# 16V2_EDA.net
KiCad netlist of a schematic drawn in EasyEDA Pro
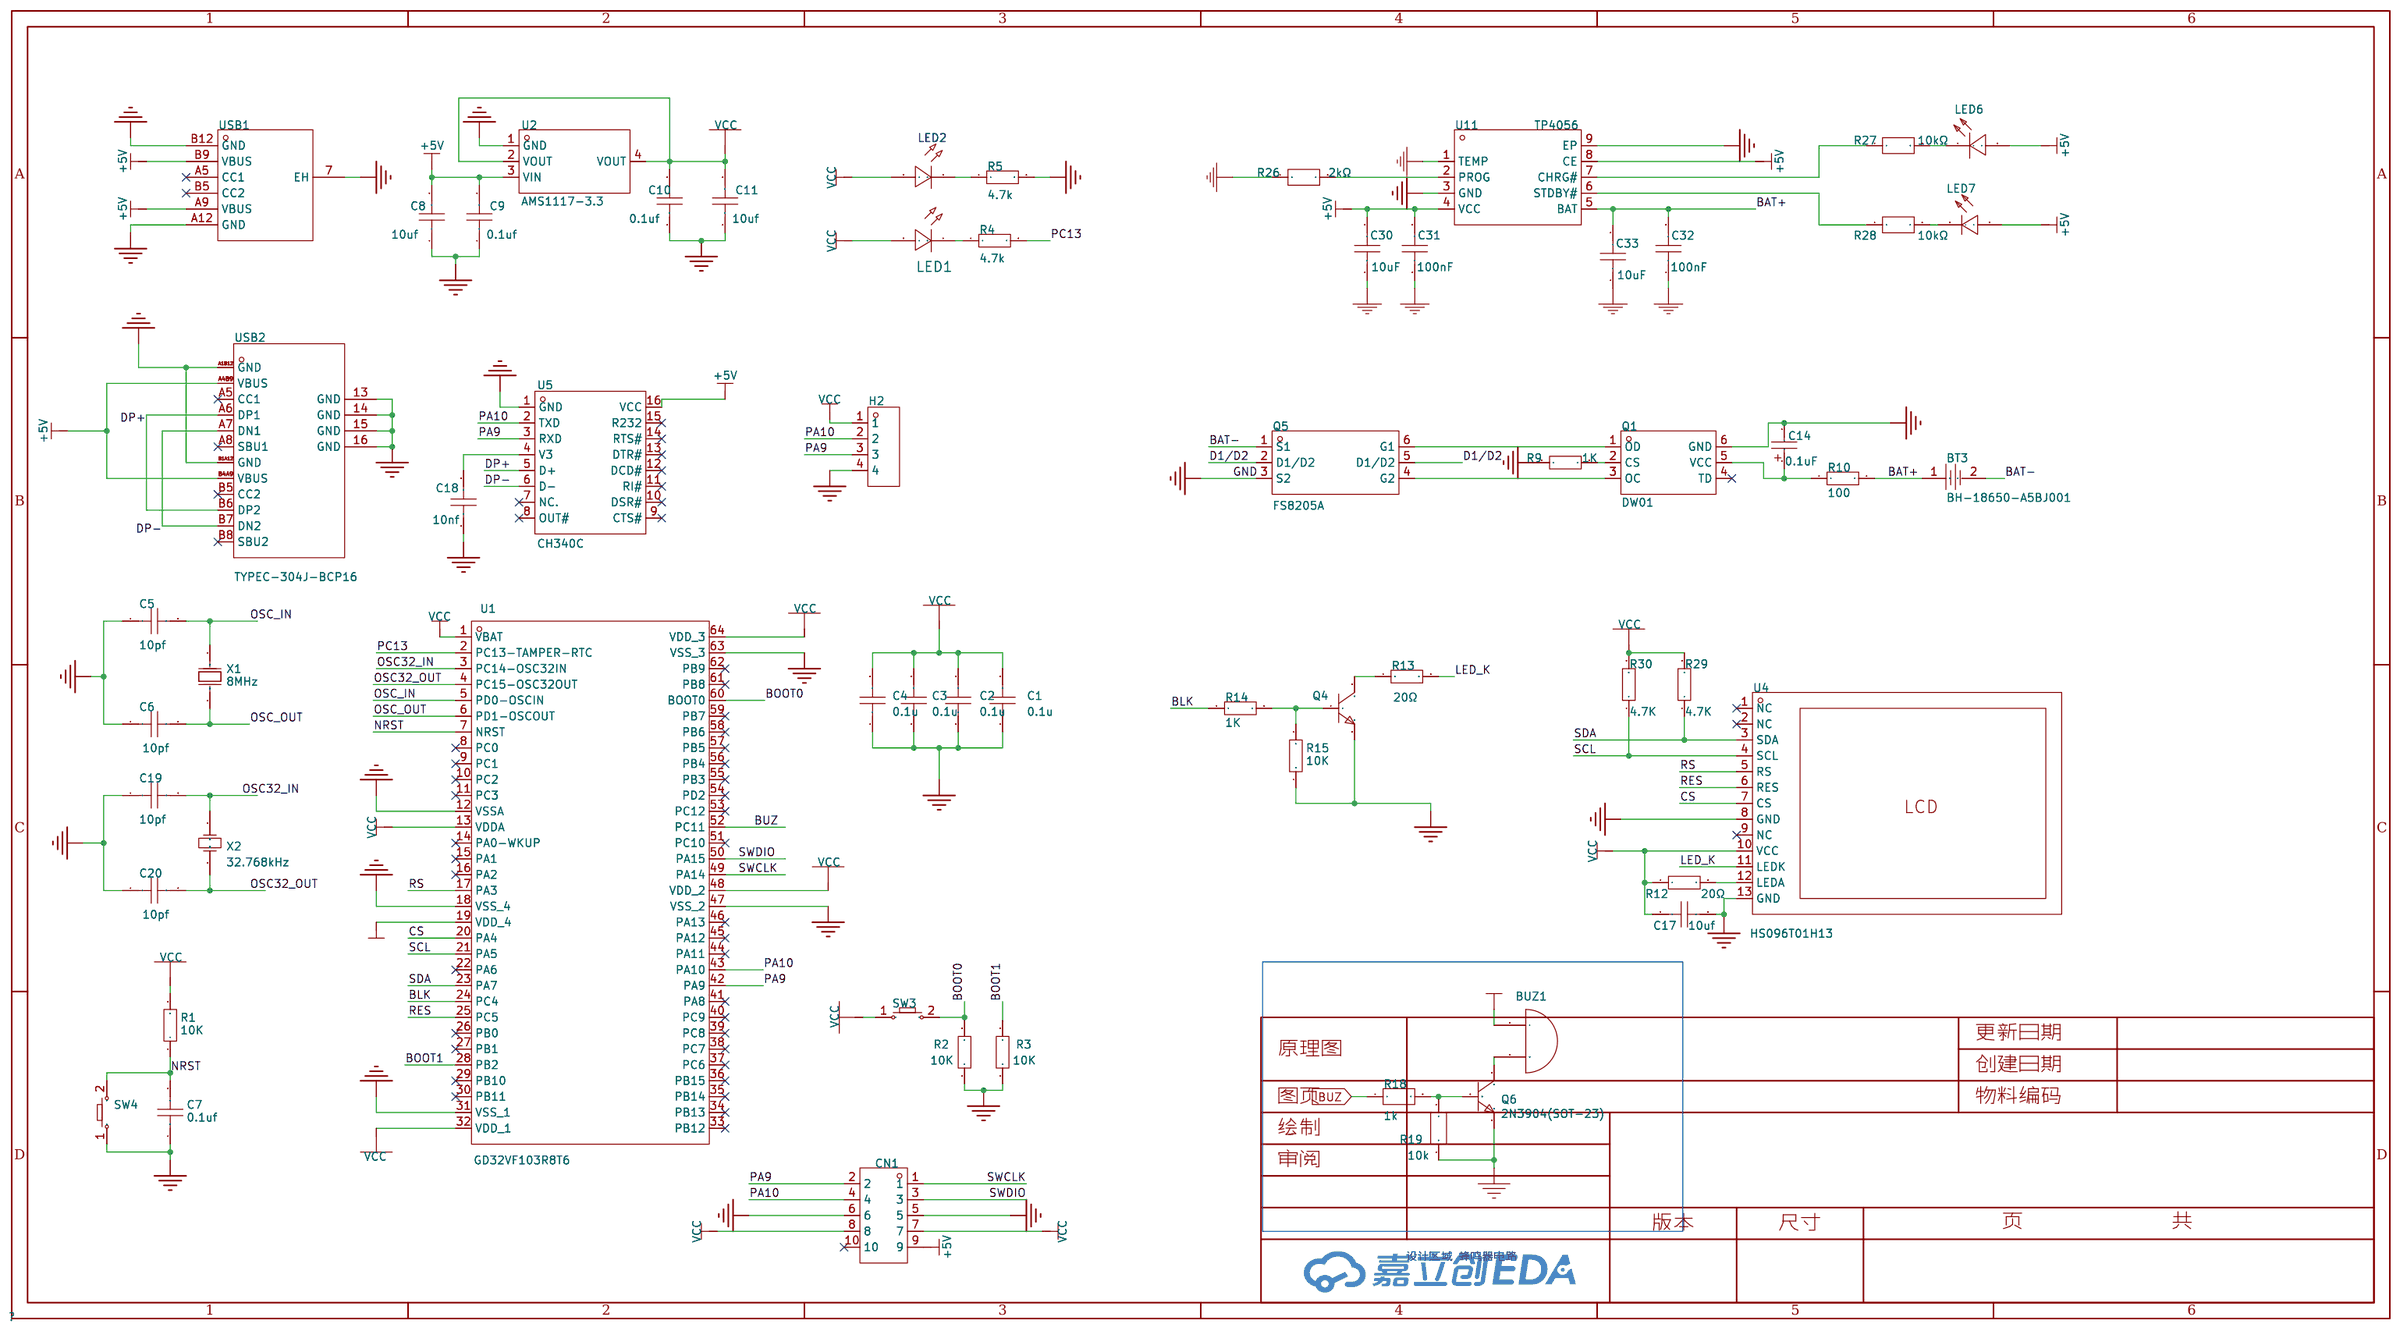
[diagram p0: schematic sheet]

(export (version "E")
  (design (tool "Eeschema 10.0.6"))
  (components
    (comp (ref "BT3")
      (value "BH-18650-A5BJ001")
      (footprint "easyedapro:BAT-TH_18650-A5BJ001")
      (description "BHNi DIP 适用电池18650电芯//电池底座/卧式DIP 电池盒/电池座 材质：PP  镀镍 ，")
      (fields (field (name "Manufacturer") "MYOUNG(美阳)"))
      (libsource (lib "easyedapro") (part "BH-18650-A5BJ001"))
    )
    (comp (ref "BUZ1") (value "BUZ1") (libsource (lib "easyedapro") (part "BUZ1")))
    (comp (ref "C1")
      (value "0.1u")
      (footprint "easyedapro:C0603")
      (libsource (lib "easyedapro") (part "capacitance"))
    )
    (comp (ref "C2")
      (value "0.1u")
      (footprint "easyedapro:C0603")
      (libsource (lib "easyedapro") (part "capacitance"))
    )
    (comp (ref "C3")
      (value "0.1u")
      (footprint "easyedapro:C0603")
      (libsource (lib "easyedapro") (part "capacitance"))
    )
    (comp (ref "C4")
      (value "0.1u")
      (footprint "easyedapro:C0603")
      (libsource (lib "easyedapro") (part "capacitance"))
    )
    (comp (ref "C5")
      (value "10pf")
      (footprint "easyedapro:C0603")
      (libsource (lib "easyedapro") (part "capacitance"))
    )
    (comp (ref "C6")
      (value "10pf")
      (footprint "easyedapro:C0603")
      (libsource (lib "easyedapro") (part "capacitance"))
    )
    (comp (ref "C7")
      (value "0.1uf")
      (footprint "easyedapro:C0603")
      (libsource (lib "easyedapro") (part "capacitance"))
    )
    (comp (ref "C8")
      (value "10uf")
      (footprint "easyedapro:C0603")
      (libsource (lib "easyedapro") (part "capacitance"))
    )
    (comp (ref "C9")
      (value "0.1uf")
      (footprint "easyedapro:C0603")
      (libsource (lib "easyedapro") (part "capacitance"))
    )
    (comp (ref "C10")
      (value "0.1uf")
      (footprint "easyedapro:C0603")
      (libsource (lib "easyedapro") (part "capacitance"))
    )
    (comp (ref "C11")
      (value "10uf")
      (footprint "easyedapro:C0603")
      (libsource (lib "easyedapro") (part "capacitance"))
    )
    (comp (ref "C14")
      (value "0.1uF")
      (footprint "easyedapro:C_Ele_SMD_3x5.4mm")
      (libsource (lib "easyedapro") (part "CAP"))
    )
    (comp (ref "C17")
      (value "10uf")
      (footprint "easyedapro:C0603")
      (libsource (lib "easyedapro") (part "capacitance"))
    )
    (comp (ref "C18")
      (value "10nf")
      (footprint "easyedapro:C0603")
      (libsource (lib "easyedapro") (part "capacitance"))
    )
    (comp (ref "C19")
      (value "10pf")
      (footprint "easyedapro:C0603")
      (libsource (lib "easyedapro") (part "capacitance"))
    )
    (comp (ref "C20")
      (value "10pf")
      (footprint "easyedapro:C0603")
      (libsource (lib "easyedapro") (part "capacitance"))
    )
    (comp (ref "C30")
      (value "10uF")
      (fields (field (name "Manufacturer") "SAMSUNG(三星)"))
      (libsource (lib "easyedapro") (part "10u"))
    )
    (comp (ref "C31")
      (value "100nF")
      (fields (field (name "Manufacturer") "YAGEO(国巨)"))
      (libsource (lib "easyedapro") (part "0.1u"))
    )
    (comp (ref "C32")
      (value "100nF")
      (fields (field (name "Manufacturer") "YAGEO(国巨)"))
      (libsource (lib "easyedapro") (part "0.1u"))
    )
    (comp (ref "C33")
      (value "10uF")
      (fields (field (name "Manufacturer") "SAMSUNG(三星)"))
      (libsource (lib "easyedapro") (part "10u"))
    )
    (comp (ref "CN1") (value "ZX-PZ2.54-2-5PZZ") (libsource (lib "easyedapro") (part "phd-2*5a_c2847737")))
    (comp (ref "H2")
      (value "2.54-1*4P反弯排针")
      (footprint "easyedapro:HDR-TH_4P-P2.54-H-M-W10.4")
      (fields (field (name "Manufacturer") "BOOMELE(博穆精密)"))
      (libsource (lib "easyedapro") (part "2.54-1*4P反弯排针"))
    )
    (comp (ref "LED1")
      (value "~")
      (footprint "easyedapro:LED_0603")
      (libsource (lib "easyedapro") (part "LED_R"))
    )
    (comp (ref "LED2")
      (value "~")
      (footprint "easyedapro:LED_0603")
      (libsource (lib "easyedapro") (part "LED_G"))
    )
    (comp (ref "LED6")
      (value "KT-0603R")
      (fields (field (name "Manufacturer") "KENTO"))
      (libsource (lib "easyedapro") (part "KT-0603R"))
    )
    (comp (ref "LED7") (value "NCD0603B1") (libsource (lib "easyedapro") (part "fc-da1608bk-470h10")))
    (comp (ref "Q1")
      (value "DW01")
      (footprint "easyedapro:SOT-23-6_L2.9-W1.6-P0.95-LS2.8-BR")
      (fields (field (name "Manufacturer") "Hottech(合科泰)"))
      (libsource (lib "easyedapro") (part "DW01"))
    )
    (comp (ref "Q4")
      (value "~")
      (footprint "easyedapro:S8050_SOT-23")
      (libsource (lib "easyedapro") (part "NPN"))
    )
    (comp (ref "Q5")
      (value "FS8205A")
      (footprint "easyedapro:SOT-23-6_L2.9-W1.6-P0.95-LS2.8-BR")
      (fields (field (name "Manufacturer") "TECH PUBLIC(台舟)"))
      (libsource (lib "easyedapro") (part "FS8205A_C2830320"))
    )
    (comp (ref "Q6")
      (value "2N3904(SOT-23)")
      (fields (field (name "Manufacturer Part") "2n3904S-RTK/PS") (field (name "Manufacturer") "KEC"))
      (libsource (lib "easyedapro") (part "2N3904(SOT-23)"))
    )
    (comp (ref "R1") (value "10K") (libsource (lib "easyedapro") (part "电阻")))
    (comp (ref "R2") (value "10K") (libsource (lib "easyedapro") (part "电阻")))
    (comp (ref "R3") (value "10K") (libsource (lib "easyedapro") (part "电阻")))
    (comp (ref "R4") (value "4.7k") (libsource (lib "easyedapro") (part "电阻")))
    (comp (ref "R5") (value "4.7k") (libsource (lib "easyedapro") (part "电阻")))
    (comp (ref "R9") (value "1K") (libsource (lib "easyedapro") (part "电阻")))
    (comp (ref "R10") (value "100") (libsource (lib "easyedapro") (part "电阻")))
    (comp (ref "R12") (value "20Ω") (libsource (lib "easyedapro") (part "电阻")))
    (comp (ref "R13") (value "20Ω") (libsource (lib "easyedapro") (part "电阻")))
    (comp (ref "R14") (value "1K") (libsource (lib "easyedapro") (part "电阻")))
    (comp (ref "R15") (value "10K") (libsource (lib "easyedapro") (part "电阻")))
    (comp (ref "R18") (value "1k") (libsource (lib "easyedapro") (part "1k")))
    (comp (ref "R19") (value "10k") (libsource (lib "easyedapro") (part "10k")))
    (comp (ref "R26")
      (value "2kΩ")
      (fields (field (name "Manufacturer") "UNI-ROYAL(厚声)"))
      (libsource (lib "easyedapro") (part "2k"))
    )
    (comp (ref "R27")
      (value "10kΩ")
      (fields (field (name "Manufacturer") "UNI-ROYAL(厚声)"))
      (libsource (lib "easyedapro") (part "10k"))
    )
    (comp (ref "R28")
      (value "10kΩ")
      (fields (field (name "Manufacturer") "UNI-ROYAL(厚声)"))
      (libsource (lib "easyedapro") (part "10k"))
    )
    (comp (ref "R29")
      (value "4.7K")
      (footprint "easyedapro:R0603")
      (libsource (lib "easyedapro") (part "电阻"))
    )
    (comp (ref "R30")
      (value "4.7K")
      (footprint "easyedapro:R0603")
      (libsource (lib "easyedapro") (part "电阻"))
    )
    (comp (ref "SW3")
      (value "~")
      (footprint "easyedapro:Key_SMD_3x4x2")
      (libsource (lib "easyedapro") (part "轻触按键x2"))
    )
    (comp (ref "SW4")
      (value "~")
      (footprint "easyedapro:Key_SMD_3x4x2")
      (libsource (lib "easyedapro") (part "轻触按键x2"))
    )
    (comp (ref "U1")
      (value "GD32VF103R8T6")
      (footprint "easyedapro:LQFP-64_L10.0-W10.0-P0.50-LS12.0-BL")
      (description "CPU内核:RISC-V;程序存储容量:64KB;RAM总容量:20KB;GPIO端口数量:51;工作电压范围:-;CPU最大主频:108MHz;程序存储器类型:FLASH;")
      (fields (field (name "Manufacturer") "GigaDevice(兆易创新)"))
      (libsource (lib "easyedapro") (part "GD32VF103R8T6"))
    )
    (comp (ref "U2")
      (value "AMS1117-3.3")
      (footprint "easyedapro:SOT-223-3_L6.5-W3.4-P2.30-LS7.0-BR")
      (description "输出类型:固定;最大输入电压:-;输出电压:3.3V;最大输出电流:1A;电源纹波抑制比(PSRR):72dB@(120Hz);输出极性:正极;")
      (fields (field (name "Manufacturer") "AMS"))
      (libsource (lib "easyedapro") (part "AMS1117-3.3"))
    )
    (comp (ref "U4")
      (value "HS096T01H13")
      (footprint "easyedapro:LCD-SMD_HS096T01H13")
      (description "主控芯片:ST7735;尺寸(inch):0.96;")
      (fields (field (name "Manufacturer") "HS(汉昇)"))
      (libsource (lib "easyedapro") (part "HS096T01H13"))
    )
    (comp (ref "U5")
      (value "CH340C")
      (footprint "easyedapro:SOP-16_L10.0-W3.9-P1.27-LS6.0-BL")
      (description "应用功能:收发器;接口协议:USB 2.0;数据速率:2Mbps;")
      (fields (field (name "Manufacturer") "WCH(南京沁恒)"))
      (libsource (lib "easyedapro") (part "CH340C"))
    )
    (comp (ref "U11")
      (value "TP4056")
      (fields (field (name "Manufacturer") "UMW(友台半导体)"))
      (libsource (lib "easyedapro") (part "TP4056_C725790"))
    )
    (comp (ref "USB1")
      (value "TYPE-C 6P")
      (footprint "easyedapro:TYPE-C-SMD_TYPE-C-6P")
      (description "连接器类型:Type-C;标准:-;公母:母;端口数量:1;触点数量:6P;安装方式:卧贴;额定电流 - 电源:-;工作温度范围:-40°C~+85°C;")
      (fields (field (name "Manufacturer") "SHOU HAN(首韩)"))
      (libsource (lib "easyedapro") (part "TYPE-C 6P"))
    )
    (comp (ref "USB2")
      (value "TYPEC-304J-BCP16")
      (footprint "easyedapro:USB-C-SMD_TYPEC-304J-BCP16")
      (fields (field (name "Manufacturer") "XUNPU(讯普)"))
      (libsource (lib "easyedapro") (part "TYPEC-304J-BCP16"))
    )
    (comp (ref "X1")
      (value "8MHz")
      (footprint "easyedapro:CRYSTAL-SMD_L11.5-W4.8-LS12.7")
      (description "晶振类型:贴片晶振;频率:8MHz;常温频差:±20ppm;外接负载电容:20pF;频率稳定度(全温):±30ppm;")
      (fields (field (name "Manufacturer Part") "X49SM8MSD2SC") (field (name "Manufacturer") "YXC(扬兴晶振)"))
      (libsource (lib "easyedapro") (part "X49SM8MSD2SC"))
    )
    (comp (ref "X2")
      (value "32.768kHz")
      (footprint "easyedapro:OSC-TH_BD3.1-P0.8-D0.3")
      (description "晶振类型:直插晶振;频率:32.768kHz;常温频差:±10ppm;外接负载电容:12.5pF;频率稳定度(全温):-;")
      (fields (field (name "Manufacturer Part") "X308032768KGB2SC") (field (name "Manufacturer") "YXC(扬兴晶振)"))
      (libsource (lib "easyedapro") (part "X308032768KGB2SC"))
    )
  )
  (nets
    (net (code "1") (name "+5V") (class "Default")
      (node (ref "C30") (pin "2") (pinfunction "2_2") (pintype "unspecified"))
      (node (ref "C31") (pin "2") (pinfunction "2_2") (pintype "unspecified"))
      (node (ref "C8") (pin "2") (pinfunction "2_2") (pintype "input"))
      (node (ref "C9") (pin "2") (pinfunction "2_2") (pintype "input"))
      (node (ref "CN1") (pin "9") (pinfunction "9_9") (pintype "unspecified"))
      (node (ref "LED6") (pin "2") (pinfunction "A_2") (pintype "unspecified"))
      (node (ref "LED7") (pin "2") (pinfunction "+_2") (pintype "input"))
      (node (ref "U11") (pin "4") (pinfunction "VCC_4") (pintype "unspecified"))
      (node (ref "U11") (pin "8") (pinfunction "CE_8") (pintype "unspecified"))
      (node (ref "U2") (pin "3") (pinfunction "VIN_3") (pintype "unspecified"))
      (node (ref "U5") (pin "16") (pinfunction "VCC_16") (pintype "unspecified"))
      (node (ref "USB1") (pin "A9") (pinfunction "VBUS_A9") (pintype "unspecified"))
      (node (ref "USB1") (pin "B9") (pinfunction "VBUS_B9") (pintype "unspecified"))
      (node (ref "USB2") (pin "A4B9") (pinfunction "VBUS_A4B9") (pintype "unspecified"))
      (node (ref "USB2") (pin "B4A9") (pinfunction "VBUS_B4A9") (pintype "unspecified"))
    )
    (net (code "2") (name "/BAT+") (class "Default")
      (node (ref "BT3") (pin "1") (pinfunction "1_1") (pintype "input"))
      (node (ref "C32") (pin "2") (pinfunction "2_2") (pintype "unspecified"))
      (node (ref "C33") (pin "2") (pinfunction "2_2") (pintype "unspecified"))
      (node (ref "R10") (pin "2") (pinfunction "2_2") (pintype "input"))
      (node (ref "U11") (pin "5") (pinfunction "BAT_5") (pintype "unspecified"))
    )
    (net (code "3") (name "/BAT-") (class "Default")
      (node (ref "BT3") (pin "2") (pinfunction "2_2") (pintype "input"))
      (node (ref "Q5") (pin "1") (pinfunction "S1_1") (pintype "unspecified"))
    )
    (net (code "4") (name "/BLK") (class "Default")
      (node (ref "R14") (pin "1") (pinfunction "1_1") (pintype "input"))
      (node (ref "U1") (pin "24") (pinfunction "PC4_24") (pintype "input"))
    )
    (net (code "5") (name "/BOOT0") (class "Default")
      (node (ref "R2") (pin "2") (pinfunction "2_2") (pintype "input"))
      (node (ref "SW3") (pin "2") (pinfunction "2_2") (pintype "input"))
      (node (ref "U1") (pin "60") (pinfunction "BOOT0_60") (pintype "input"))
    )
    (net (code "6") (name "/BOOT1") (class "Default")
      (node (ref "R3") (pin "2") (pinfunction "2_2") (pintype "input"))
      (node (ref "U1") (pin "28") (pinfunction "PB2_28") (pintype "input"))
    )
    (net (code "7") (name "/CS") (class "Default")
      (node (ref "U1") (pin "20") (pinfunction "PA4_20") (pintype "input"))
      (node (ref "U4") (pin "7") (pinfunction "CS_7") (pintype "unspecified"))
    )
    (net (code "8") (name "/D1{slash}D2") (class "Default")
      (node (ref "Q5") (pin "2") (pinfunction "D1/D2_2") (pintype "unspecified"))
      (node (ref "Q5") (pin "5") (pinfunction "D1/D2_5") (pintype "unspecified"))
    )
    (net (code "9") (name "/DP+") (class "Default")
      (node (ref "U5") (pin "5") (pinfunction "D+_5") (pintype "unspecified"))
      (node (ref "USB2") (pin "A6") (pinfunction "DP1_A6") (pintype "unspecified"))
      (node (ref "USB2") (pin "B6") (pinfunction "DP2_B6") (pintype "unspecified"))
    )
    (net (code "10") (name "/DP-") (class "Default")
      (node (ref "U5") (pin "6") (pinfunction "D-_6") (pintype "unspecified"))
      (node (ref "USB2") (pin "A7") (pinfunction "DN1_A7") (pintype "unspecified"))
      (node (ref "USB2") (pin "B7") (pinfunction "DN2_B7") (pintype "unspecified"))
    )
    (net (code "11") (name "/LED_K") (class "Default")
      (node (ref "R13") (pin "2") (pinfunction "2_2") (pintype "input"))
      (node (ref "U4") (pin "11") (pinfunction "LEDK_11") (pintype "unspecified"))
    )
    (net (code "12") (name "/NRST") (class "Default")
      (node (ref "C7") (pin "2") (pinfunction "2_2") (pintype "input"))
      (node (ref "R1") (pin "1") (pinfunction "1_1") (pintype "input"))
      (node (ref "SW4") (pin "2") (pinfunction "2_2") (pintype "input"))
      (node (ref "U1") (pin "7") (pinfunction "NRST_7") (pintype "input"))
    )
    (net (code "13") (name "/OSC32_IN") (class "Default")
      (node (ref "C19") (pin "2") (pinfunction "2_2") (pintype "input"))
      (node (ref "U1") (pin "3") (pinfunction "PC14-OSC32IN_3") (pintype "input"))
      (node (ref "X2") (pin "1") (pinfunction "OSC1_1") (pintype "unspecified"))
    )
    (net (code "14") (name "/OSC32_OUT") (class "Default")
      (node (ref "C20") (pin "2") (pinfunction "2_2") (pintype "input"))
      (node (ref "U1") (pin "4") (pinfunction "PC15-OSC32OUT_4") (pintype "input"))
      (node (ref "X2") (pin "2") (pinfunction "OSC2_2") (pintype "unspecified"))
    )
    (net (code "15") (name "/OSC_IN") (class "Default")
      (node (ref "C5") (pin "2") (pinfunction "2_2") (pintype "input"))
      (node (ref "U1") (pin "5") (pinfunction "PD0-OSCIN_5") (pintype "input"))
      (node (ref "X1") (pin "1") (pinfunction "OSC1_1") (pintype "input"))
    )
    (net (code "16") (name "/OSC_OUT") (class "Default")
      (node (ref "C6") (pin "2") (pinfunction "2_2") (pintype "input"))
      (node (ref "U1") (pin "6") (pinfunction "PD1-OSCOUT_6") (pintype "input"))
      (node (ref "X1") (pin "2") (pinfunction "OSC2_2") (pintype "input"))
    )
    (net (code "17") (name "/PA9") (class "Default")
      (node (ref "CN1") (pin "2") (pinfunction "2_2") (pintype "unspecified"))
      (node (ref "H2") (pin "3") (pinfunction "3_3") (pintype "unspecified"))
      (node (ref "U1") (pin "42") (pinfunction "PA9_42") (pintype "input"))
      (node (ref "U5") (pin "3") (pinfunction "RXD_3") (pintype "unspecified"))
    )
    (net (code "18") (name "/PA10") (class "Default")
      (node (ref "CN1") (pin "4") (pinfunction "4_4") (pintype "unspecified"))
      (node (ref "H2") (pin "2") (pinfunction "2_2") (pintype "unspecified"))
      (node (ref "U1") (pin "43") (pinfunction "PA10_43") (pintype "input"))
      (node (ref "U5") (pin "2") (pinfunction "TXD_2") (pintype "unspecified"))
    )
    (net (code "19") (name "/PC13") (class "Default")
      (node (ref "R4") (pin "2") (pinfunction "2_2") (pintype "input"))
      (node (ref "U1") (pin "2") (pinfunction "PC13-TAMPER-RTC_2") (pintype "input"))
    )
    (net (code "20") (name "/RES") (class "Default")
      (node (ref "U1") (pin "25") (pinfunction "PC5_25") (pintype "input"))
      (node (ref "U4") (pin "6") (pinfunction "RES_6") (pintype "unspecified"))
    )
    (net (code "21") (name "/RS") (class "Default")
      (node (ref "U1") (pin "17") (pinfunction "PA3_17") (pintype "input"))
      (node (ref "U4") (pin "5") (pinfunction "RS_5") (pintype "unspecified"))
    )
    (net (code "22") (name "/SCL") (class "Default")
      (node (ref "R30") (pin "1") (pinfunction "1_1") (pintype "input"))
      (node (ref "U1") (pin "21") (pinfunction "PA5_21") (pintype "input"))
      (node (ref "U4") (pin "4") (pinfunction "SCL_4") (pintype "unspecified"))
    )
    (net (code "23") (name "/SDA") (class "Default")
      (node (ref "R29") (pin "1") (pinfunction "1_1") (pintype "input"))
      (node (ref "U1") (pin "23") (pinfunction "PA7_23") (pintype "input"))
      (node (ref "U4") (pin "3") (pinfunction "SDA_3") (pintype "unspecified"))
    )
    (net (code "24") (name "/SWCLK") (class "Default")
      (node (ref "CN1") (pin "1") (pinfunction "1_1") (pintype "unspecified"))
      (node (ref "U1") (pin "49") (pinfunction "PA14_49") (pintype "input"))
    )
    (net (code "25") (name "/SWDIO") (class "Default")
      (node (ref "CN1") (pin "3") (pinfunction "3_3") (pintype "unspecified"))
      (node (ref "U1") (pin "50") (pinfunction "PA15_50") (pintype "input"))
    )
    (net (code "26") (name "BUZ") (class "Default")
      (node (ref "R18") (pin "1") (pinfunction "1_1") (pintype "input"))
      (node (ref "U1") (pin "52") (pinfunction "PC11_52") (pintype "input"))
    )
    (net (code "27") (name "GND") (class "Default")
      (node (ref "C1") (pin "1") (pinfunction "1_1") (pintype "input"))
      (node (ref "C10") (pin "1") (pinfunction "1_1") (pintype "input"))
      (node (ref "C11") (pin "1") (pinfunction "1_1") (pintype "input"))
      (node (ref "C14") (pin "2") (pinfunction "2_2") (pintype "input"))
      (node (ref "C17") (pin "2") (pinfunction "2_2") (pintype "input"))
      (node (ref "C18") (pin "1") (pinfunction "1_1") (pintype "input"))
      (node (ref "C19") (pin "1") (pinfunction "1_1") (pintype "input"))
      (node (ref "C2") (pin "1") (pinfunction "1_1") (pintype "input"))
      (node (ref "C20") (pin "1") (pinfunction "1_1") (pintype "input"))
      (node (ref "C3") (pin "1") (pinfunction "1_1") (pintype "input"))
      (node (ref "C30") (pin "1") (pinfunction "1_1") (pintype "unspecified"))
      (node (ref "C31") (pin "1") (pinfunction "1_1") (pintype "unspecified"))
      (node (ref "C32") (pin "1") (pinfunction "1_1") (pintype "unspecified"))
      (node (ref "C33") (pin "1") (pinfunction "1_1") (pintype "unspecified"))
      (node (ref "C4") (pin "1") (pinfunction "1_1") (pintype "input"))
      (node (ref "C5") (pin "1") (pinfunction "1_1") (pintype "input"))
      (node (ref "C6") (pin "1") (pinfunction "1_1") (pintype "input"))
      (node (ref "C7") (pin "1") (pinfunction "1_1") (pintype "input"))
      (node (ref "C8") (pin "1") (pinfunction "1_1") (pintype "input"))
      (node (ref "C9") (pin "1") (pinfunction "1_1") (pintype "input"))
      (node (ref "CN1") (pin "5") (pinfunction "5_5") (pintype "unspecified"))
      (node (ref "CN1") (pin "6") (pinfunction "6_6") (pintype "unspecified"))
      (node (ref "H2") (pin "4") (pinfunction "4_4") (pintype "unspecified"))
      (node (ref "Q1") (pin "6") (pinfunction "GND_6") (pintype "input"))
      (node (ref "Q4") (pin "2") (pinfunction "2_2") (pintype "unspecified"))
      (node (ref "Q5") (pin "3") (pinfunction "S2_3") (pintype "unspecified"))
      (node (ref "Q6") (pin "1") (pinfunction "E_1") (pintype "input"))
      (node (ref "R15") (pin "1") (pinfunction "1_1") (pintype "input"))
      (node (ref "R19") (pin "2") (pinfunction "2_2") (pintype "unspecified"))
      (node (ref "R2") (pin "1") (pinfunction "1_1") (pintype "input"))
      (node (ref "R26") (pin "1") (pinfunction "1_1") (pintype "unspecified"))
      (node (ref "R3") (pin "1") (pinfunction "1_1") (pintype "input"))
      (node (ref "R5") (pin "2") (pinfunction "2_2") (pintype "input"))
      (node (ref "R9") (pin "1") (pinfunction "1_1") (pintype "input"))
      (node (ref "SW4") (pin "1") (pinfunction "1_1") (pintype "input"))
      (node (ref "U1") (pin "12") (pinfunction "VSSA_12") (pintype "input"))
      (node (ref "U1") (pin "18") (pinfunction "VSS_4_18") (pintype "input"))
      (node (ref "U1") (pin "31") (pinfunction "VSS_1_31") (pintype "input"))
      (node (ref "U1") (pin "47") (pinfunction "VSS_2_47") (pintype "input"))
      (node (ref "U1") (pin "63") (pinfunction "VSS_3_63") (pintype "input"))
      (node (ref "U11") (pin "1") (pinfunction "TEMP_1") (pintype "unspecified"))
      (node (ref "U11") (pin "3") (pinfunction "GND_3") (pintype "unspecified"))
      (node (ref "U11") (pin "9") (pinfunction "EP_9") (pintype "unspecified"))
      (node (ref "U2") (pin "1") (pinfunction "GND_1") (pintype "unspecified"))
      (node (ref "U4") (pin "13") (pinfunction "GND_13") (pintype "unspecified"))
      (node (ref "U4") (pin "8") (pinfunction "GND_8") (pintype "unspecified"))
      (node (ref "U5") (pin "1") (pinfunction "GND_1") (pintype "unspecified"))
      (node (ref "USB1") (pin "7") (pinfunction "EH_7") (pintype "unspecified"))
      (node (ref "USB1") (pin "A12") (pinfunction "GND_A12") (pintype "unspecified"))
      (node (ref "USB1") (pin "B12") (pinfunction "GND_B12") (pintype "unspecified"))
      (node (ref "USB2") (pin "13") (pinfunction "GND_13") (pintype "unspecified"))
      (node (ref "USB2") (pin "14") (pinfunction "GND_14") (pintype "unspecified"))
      (node (ref "USB2") (pin "15") (pinfunction "GND_15") (pintype "unspecified"))
      (node (ref "USB2") (pin "16") (pinfunction "GND_16") (pintype "unspecified"))
      (node (ref "USB2") (pin "A1B12") (pinfunction "GND_A1B12") (pintype "unspecified"))
      (node (ref "USB2") (pin "B1A12") (pinfunction "GND_B1A12") (pintype "unspecified"))
    )
    (net (code "28") (name "Net-(BUZ1-B)") (class "Default")
      (node (ref "BUZ1") (pin "2") (pinfunction "B_2") (pintype "input"))
      (node (ref "Q6") (pin "3") (pinfunction "C_3") (pintype "input"))
    )
    (net (code "29") (name "Net-(LED1-C)") (class "Default")
      (node (ref "LED1") (pin "1") (pinfunction "C_1") (pintype "input"))
      (node (ref "R4") (pin "1") (pinfunction "1_1") (pintype "input"))
    )
    (net (code "30") (name "Net-(LED2-C)") (class "Default")
      (node (ref "LED2") (pin "1") (pinfunction "C_1") (pintype "input"))
      (node (ref "R5") (pin "1") (pinfunction "1_1") (pintype "input"))
    )
    (net (code "31") (name "Net-(LED6-K)") (class "Default")
      (node (ref "LED6") (pin "1") (pinfunction "K_1") (pintype "unspecified"))
      (node (ref "R27") (pin "2") (pinfunction "2_2") (pintype "unspecified"))
    )
    (net (code "32") (name "Net-(LED7--)") (class "Default")
      (node (ref "LED7") (pin "1") (pinfunction "-_1") (pintype "input"))
      (node (ref "R28") (pin "2") (pinfunction "2_2") (pintype "unspecified"))
    )
    (net (code "33") (name "Net-(Q1-CS)") (class "Default")
      (node (ref "Q1") (pin "2") (pinfunction "CS_2") (pintype "input"))
      (node (ref "R9") (pin "2") (pinfunction "2_2") (pintype "input"))
    )
    (net (code "34") (name "Net-(Q1-OC)") (class "Default")
      (node (ref "Q1") (pin "3") (pinfunction "OC_3") (pintype "input"))
      (node (ref "Q5") (pin "4") (pinfunction "G2_4") (pintype "unspecified"))
    )
    (net (code "35") (name "Net-(Q1-OD)") (class "Default")
      (node (ref "Q1") (pin "1") (pinfunction "OD_1") (pintype "input"))
      (node (ref "Q5") (pin "6") (pinfunction "G1_6") (pintype "unspecified"))
    )
    (net (code "36") (name "Net-(Q1-VCC)") (class "Default")
      (node (ref "C14") (pin "1") (pinfunction "1_1") (pintype "input"))
      (node (ref "Q1") (pin "5") (pinfunction "VCC_5") (pintype "input"))
      (node (ref "R10") (pin "1") (pinfunction "1_1") (pintype "input"))
    )
    (net (code "37") (name "Net-(Q4-Pad1)") (class "Default")
      (node (ref "Q4") (pin "1") (pinfunction "1_1") (pintype "unspecified"))
      (node (ref "R14") (pin "2") (pinfunction "2_2") (pintype "input"))
      (node (ref "R15") (pin "2") (pinfunction "2_2") (pintype "input"))
    )
    (net (code "38") (name "Net-(Q4-Pad3)") (class "Default")
      (node (ref "Q4") (pin "3") (pinfunction "3_3") (pintype "unspecified"))
      (node (ref "R13") (pin "1") (pinfunction "1_1") (pintype "input"))
    )
    (net (code "39") (name "Net-(Q6-B)") (class "Default")
      (node (ref "Q6") (pin "2") (pinfunction "B_2") (pintype "input"))
      (node (ref "R18") (pin "2") (pinfunction "2_2") (pintype "input"))
      (node (ref "R19") (pin "1") (pinfunction "1_1") (pintype "unspecified"))
    )
    (net (code "40") (name "Net-(U4-LEDA)") (class "Default")
      (node (ref "R12") (pin "2") (pinfunction "2_2") (pintype "input"))
      (node (ref "U4") (pin "12") (pinfunction "LEDA_12") (pintype "unspecified"))
    )
    (net (code "41") (name "Net-(U5-V3)") (class "Default")
      (node (ref "C18") (pin "2") (pinfunction "2_2") (pintype "input"))
      (node (ref "U5") (pin "4") (pinfunction "V3_4") (pintype "unspecified"))
    )
    (net (code "42") (name "Net-(U11-CHRG#)") (class "Default")
      (node (ref "R27") (pin "1") (pinfunction "1_1") (pintype "unspecified"))
      (node (ref "U11") (pin "7") (pinfunction "CHRG#_7") (pintype "unspecified"))
    )
    (net (code "43") (name "Net-(U11-PROG)") (class "Default")
      (node (ref "R26") (pin "2") (pinfunction "2_2") (pintype "unspecified"))
      (node (ref "U11") (pin "2") (pinfunction "PROG_2") (pintype "unspecified"))
    )
    (net (code "44") (name "Net-(U11-STDBY#)") (class "Default")
      (node (ref "R28") (pin "1") (pinfunction "1_1") (pintype "unspecified"))
      (node (ref "U11") (pin "6") (pinfunction "STDBY#_6") (pintype "unspecified"))
    )
    (net (code "45") (name "VCC") (class "Default")
      (node (ref "BUZ1") (pin "1") (pinfunction "A_1") (pintype "input"))
      (node (ref "C1") (pin "2") (pinfunction "2_2") (pintype "input"))
      (node (ref "C10") (pin "2") (pinfunction "2_2") (pintype "input"))
      (node (ref "C11") (pin "2") (pinfunction "2_2") (pintype "input"))
      (node (ref "C17") (pin "1") (pinfunction "1_1") (pintype "input"))
      (node (ref "C2") (pin "2") (pinfunction "2_2") (pintype "input"))
      (node (ref "C3") (pin "2") (pinfunction "2_2") (pintype "input"))
      (node (ref "C4") (pin "2") (pinfunction "2_2") (pintype "input"))
      (node (ref "CN1") (pin "7") (pinfunction "7_7") (pintype "unspecified"))
      (node (ref "CN1") (pin "8") (pinfunction "8_8") (pintype "unspecified"))
      (node (ref "H2") (pin "1") (pinfunction "1_1") (pintype "unspecified"))
      (node (ref "LED1") (pin "2") (pinfunction "A_2") (pintype "input"))
      (node (ref "LED2") (pin "2") (pinfunction "A_2") (pintype "input"))
      (node (ref "R1") (pin "2") (pinfunction "2_2") (pintype "input"))
      (node (ref "R12") (pin "1") (pinfunction "1_1") (pintype "input"))
      (node (ref "R29") (pin "2") (pinfunction "2_2") (pintype "input"))
      (node (ref "R30") (pin "2") (pinfunction "2_2") (pintype "input"))
      (node (ref "SW3") (pin "1") (pinfunction "1_1") (pintype "input"))
      (node (ref "U1") (pin "1") (pinfunction "VBAT_1") (pintype "input"))
      (node (ref "U1") (pin "13") (pinfunction "VDDA_13") (pintype "input"))
      (node (ref "U1") (pin "19") (pinfunction "VDD_4_19") (pintype "input"))
      (node (ref "U1") (pin "32") (pinfunction "VDD_1_32") (pintype "input"))
      (node (ref "U1") (pin "48") (pinfunction "VDD_2_48") (pintype "input"))
      (node (ref "U1") (pin "64") (pinfunction "VDD_3_64") (pintype "input"))
      (node (ref "U2") (pin "2") (pinfunction "VOUT_2") (pintype "unspecified"))
      (node (ref "U2") (pin "4") (pinfunction "VOUT_4") (pintype "unspecified"))
      (node (ref "U4") (pin "10") (pinfunction "VCC_10") (pintype "unspecified"))
    )
    (net (code "46") (name "unconnected-(CN1-Pad10)") (class "Default")
      (node (ref "CN1") (pin "10") (pinfunction "10_10") (pintype "unspecified+no_connect"))
    )
    (net (code "47") (name "unconnected-(Q1-TD-Pad4)") (class "Default")
      (node (ref "Q1") (pin "4") (pinfunction "TD_4") (pintype "input+no_connect"))
    )
    (net (code "48") (name "unconnected-(U1-PA0-WKUP-Pad14)") (class "Default")
      (node (ref "U1") (pin "14") (pinfunction "PA0-WKUP_14") (pintype "input+no_connect"))
    )
    (net (code "49") (name "unconnected-(U1-PA1-Pad15)") (class "Default")
      (node (ref "U1") (pin "15") (pinfunction "PA1_15") (pintype "input+no_connect"))
    )
    (net (code "50") (name "unconnected-(U1-PA2-Pad16)") (class "Default")
      (node (ref "U1") (pin "16") (pinfunction "PA2_16") (pintype "input+no_connect"))
    )
    (net (code "51") (name "unconnected-(U1-PA6-Pad22)") (class "Default")
      (node (ref "U1") (pin "22") (pinfunction "PA6_22") (pintype "input+no_connect"))
    )
    (net (code "52") (name "unconnected-(U1-PA8-Pad41)") (class "Default")
      (node (ref "U1") (pin "41") (pinfunction "PA8_41") (pintype "input+no_connect"))
    )
    (net (code "53") (name "unconnected-(U1-PA11-Pad44)") (class "Default")
      (node (ref "U1") (pin "44") (pinfunction "PA11_44") (pintype "input+no_connect"))
    )
    (net (code "54") (name "unconnected-(U1-PA12-Pad45)") (class "Default")
      (node (ref "U1") (pin "45") (pinfunction "PA12_45") (pintype "input+no_connect"))
    )
    (net (code "55") (name "unconnected-(U1-PA13-Pad46)") (class "Default")
      (node (ref "U1") (pin "46") (pinfunction "PA13_46") (pintype "input+no_connect"))
    )
    (net (code "56") (name "unconnected-(U1-PB0-Pad26)") (class "Default")
      (node (ref "U1") (pin "26") (pinfunction "PB0_26") (pintype "input+no_connect"))
    )
    (net (code "57") (name "unconnected-(U1-PB1-Pad27)") (class "Default")
      (node (ref "U1") (pin "27") (pinfunction "PB1_27") (pintype "input+no_connect"))
    )
    (net (code "58") (name "unconnected-(U1-PB3-Pad55)") (class "Default")
      (node (ref "U1") (pin "55") (pinfunction "PB3_55") (pintype "input+no_connect"))
    )
    (net (code "59") (name "unconnected-(U1-PB4-Pad56)") (class "Default")
      (node (ref "U1") (pin "56") (pinfunction "PB4_56") (pintype "input+no_connect"))
    )
    (net (code "60") (name "unconnected-(U1-PB5-Pad57)") (class "Default")
      (node (ref "U1") (pin "57") (pinfunction "PB5_57") (pintype "input+no_connect"))
    )
    (net (code "61") (name "unconnected-(U1-PB6-Pad58)") (class "Default")
      (node (ref "U1") (pin "58") (pinfunction "PB6_58") (pintype "input+no_connect"))
    )
    (net (code "62") (name "unconnected-(U1-PB7-Pad59)") (class "Default")
      (node (ref "U1") (pin "59") (pinfunction "PB7_59") (pintype "input+no_connect"))
    )
    (net (code "63") (name "unconnected-(U1-PB8-Pad61)") (class "Default")
      (node (ref "U1") (pin "61") (pinfunction "PB8_61") (pintype "input+no_connect"))
    )
    (net (code "64") (name "unconnected-(U1-PB9-Pad62)") (class "Default")
      (node (ref "U1") (pin "62") (pinfunction "PB9_62") (pintype "input+no_connect"))
    )
    (net (code "65") (name "unconnected-(U1-PB10-Pad29)") (class "Default")
      (node (ref "U1") (pin "29") (pinfunction "PB10_29") (pintype "input+no_connect"))
    )
    (net (code "66") (name "unconnected-(U1-PB11-Pad30)") (class "Default")
      (node (ref "U1") (pin "30") (pinfunction "PB11_30") (pintype "input+no_connect"))
    )
    (net (code "67") (name "unconnected-(U1-PB12-Pad33)") (class "Default")
      (node (ref "U1") (pin "33") (pinfunction "PB12_33") (pintype "input+no_connect"))
    )
    (net (code "68") (name "unconnected-(U1-PB13-Pad34)") (class "Default")
      (node (ref "U1") (pin "34") (pinfunction "PB13_34") (pintype "input+no_connect"))
    )
    (net (code "69") (name "unconnected-(U1-PB14-Pad35)") (class "Default")
      (node (ref "U1") (pin "35") (pinfunction "PB14_35") (pintype "input+no_connect"))
    )
    (net (code "70") (name "unconnected-(U1-PB15-Pad36)") (class "Default")
      (node (ref "U1") (pin "36") (pinfunction "PB15_36") (pintype "input+no_connect"))
    )
    (net (code "71") (name "unconnected-(U1-PC0-Pad8)") (class "Default")
      (node (ref "U1") (pin "8") (pinfunction "PC0_8") (pintype "input+no_connect"))
    )
    (net (code "72") (name "unconnected-(U1-PC1-Pad9)") (class "Default")
      (node (ref "U1") (pin "9") (pinfunction "PC1_9") (pintype "input+no_connect"))
    )
    (net (code "73") (name "unconnected-(U1-PC2-Pad10)") (class "Default")
      (node (ref "U1") (pin "10") (pinfunction "PC2_10") (pintype "input+no_connect"))
    )
    (net (code "74") (name "unconnected-(U1-PC3-Pad11)") (class "Default")
      (node (ref "U1") (pin "11") (pinfunction "PC3_11") (pintype "input+no_connect"))
    )
    (net (code "75") (name "unconnected-(U1-PC6-Pad37)") (class "Default")
      (node (ref "U1") (pin "37") (pinfunction "PC6_37") (pintype "input+no_connect"))
    )
    (net (code "76") (name "unconnected-(U1-PC7-Pad38)") (class "Default")
      (node (ref "U1") (pin "38") (pinfunction "PC7_38") (pintype "input+no_connect"))
    )
    (net (code "77") (name "unconnected-(U1-PC8-Pad39)") (class "Default")
      (node (ref "U1") (pin "39") (pinfunction "PC8_39") (pintype "input+no_connect"))
    )
    (net (code "78") (name "unconnected-(U1-PC9-Pad40)") (class "Default")
      (node (ref "U1") (pin "40") (pinfunction "PC9_40") (pintype "input+no_connect"))
    )
    (net (code "79") (name "unconnected-(U1-PC10-Pad51)") (class "Default")
      (node (ref "U1") (pin "51") (pinfunction "PC10_51") (pintype "input+no_connect"))
    )
    (net (code "80") (name "unconnected-(U1-PC12-Pad53)") (class "Default")
      (node (ref "U1") (pin "53") (pinfunction "PC12_53") (pintype "input+no_connect"))
    )
    (net (code "81") (name "unconnected-(U1-PD2-Pad54)") (class "Default")
      (node (ref "U1") (pin "54") (pinfunction "PD2_54") (pintype "input+no_connect"))
    )
    (net (code "82") (name "unconnected-(U4-NC-Pad1)") (class "Default")
      (node (ref "U4") (pin "1") (pinfunction "NC_1") (pintype "unspecified+no_connect"))
    )
    (net (code "83") (name "unconnected-(U4-NC-Pad2)") (class "Default")
      (node (ref "U4") (pin "2") (pinfunction "NC_2") (pintype "unspecified+no_connect"))
    )
    (net (code "84") (name "unconnected-(U4-NC-Pad9)") (class "Default")
      (node (ref "U4") (pin "9") (pinfunction "NC_9") (pintype "unspecified+no_connect"))
    )
    (net (code "85") (name "unconnected-(U5-CTS#-Pad9)") (class "Default")
      (node (ref "U5") (pin "9") (pinfunction "CTS#_9") (pintype "unspecified+no_connect"))
    )
    (net (code "86") (name "unconnected-(U5-DCD#-Pad12)") (class "Default")
      (node (ref "U5") (pin "12") (pinfunction "DCD#_12") (pintype "unspecified+no_connect"))
    )
    (net (code "87") (name "unconnected-(U5-DSR#-Pad10)") (class "Default")
      (node (ref "U5") (pin "10") (pinfunction "DSR#_10") (pintype "unspecified+no_connect"))
    )
    (net (code "88") (name "unconnected-(U5-DTR#-Pad13)") (class "Default")
      (node (ref "U5") (pin "13") (pinfunction "DTR#_13") (pintype "unspecified+no_connect"))
    )
    (net (code "89") (name "unconnected-(U5-NC.-Pad7)") (class "Default")
      (node (ref "U5") (pin "7") (pinfunction "NC._7") (pintype "unspecified+no_connect"))
    )
    (net (code "90") (name "unconnected-(U5-OUT#-Pad8)") (class "Default")
      (node (ref "U5") (pin "8") (pinfunction "OUT#_8") (pintype "unspecified+no_connect"))
    )
    (net (code "91") (name "unconnected-(U5-R232-Pad15)") (class "Default")
      (node (ref "U5") (pin "15") (pinfunction "R232_15") (pintype "unspecified+no_connect"))
    )
    (net (code "92") (name "unconnected-(U5-RI#-Pad11)") (class "Default")
      (node (ref "U5") (pin "11") (pinfunction "RI#_11") (pintype "unspecified+no_connect"))
    )
    (net (code "93") (name "unconnected-(U5-RTS#-Pad14)") (class "Default")
      (node (ref "U5") (pin "14") (pinfunction "RTS#_14") (pintype "unspecified+no_connect"))
    )
    (net (code "94") (name "unconnected-(USB1-CC1-PadA5)") (class "Default")
      (node (ref "USB1") (pin "A5") (pinfunction "CC1_A5") (pintype "unspecified+no_connect"))
    )
    (net (code "95") (name "unconnected-(USB1-CC2-PadB5)") (class "Default")
      (node (ref "USB1") (pin "B5") (pinfunction "CC2_B5") (pintype "unspecified+no_connect"))
    )
    (net (code "96") (name "unconnected-(USB2-CC1-PadA5)") (class "Default")
      (node (ref "USB2") (pin "A5") (pinfunction "CC1_A5") (pintype "unspecified+no_connect"))
    )
    (net (code "97") (name "unconnected-(USB2-CC2-PadB5)") (class "Default")
      (node (ref "USB2") (pin "B5") (pinfunction "CC2_B5") (pintype "unspecified+no_connect"))
    )
    (net (code "98") (name "unconnected-(USB2-SBU1-PadA8)") (class "Default")
      (node (ref "USB2") (pin "A8") (pinfunction "SBU1_A8") (pintype "unspecified+no_connect"))
    )
    (net (code "99") (name "unconnected-(USB2-SBU2-PadB8)") (class "Default")
      (node (ref "USB2") (pin "B8") (pinfunction "SBU2_B8") (pintype "unspecified+no_connect"))
    )
  )
)
